# cs301_template.net
KiCad netlist of a schematic drawn in Altium Designer
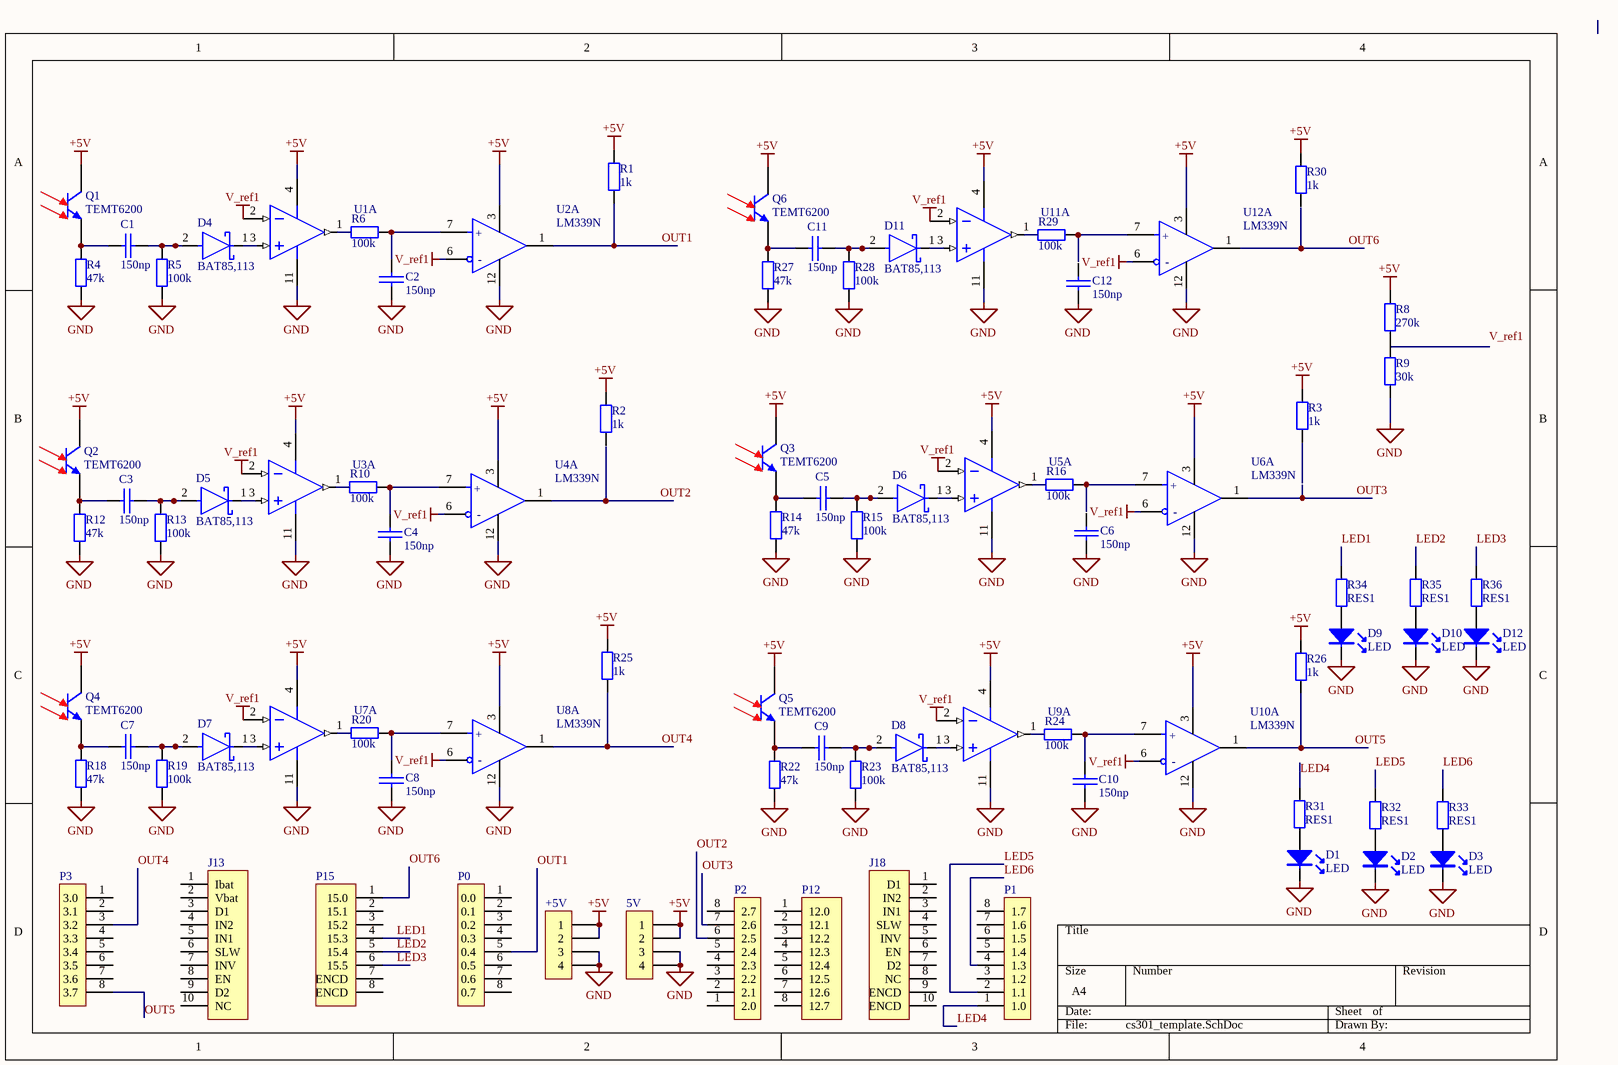
[diagram p0: cs301_template.SchDoc]

(export (version "E")
  (design (tool "Eeschema 10.0.6"))
  (components
    (comp (ref "+5V")
      (value "5V")
      (footprint "IDC4")
      (description "Connector")
      (libsource (lib "Miscellaneous Devices") (part "CON4"))
    )
    (comp (ref "5V")
      (value "5V")
      (footprint "IDC4")
      (description "Connector")
      (libsource (lib "Miscellaneous Devices") (part "CON4"))
    )
    (comp (ref "C1")
      (value "150np")
      (footprint "CCAP-5P0")
      (description "TH ceramic capacitor with 5mm pitch")
      (libsource (lib "COMSYS301_2025") (part "CerCap_TH_5P0"))
    )
    (comp (ref "C2")
      (value "150np")
      (footprint "CCAP-5P0")
      (description "TH ceramic capacitor with 5mm pitch")
      (libsource (lib "COMSYS301_2025") (part "CerCap_TH_5P0"))
    )
    (comp (ref "C3")
      (value "150np")
      (footprint "CCAP-5P0")
      (description "TH ceramic capacitor with 5mm pitch")
      (libsource (lib "COMSYS301_2025") (part "CerCap_TH_5P0"))
    )
    (comp (ref "C4")
      (value "150np")
      (footprint "CCAP-5P0")
      (description "TH ceramic capacitor with 5mm pitch")
      (libsource (lib "COMSYS301_2025") (part "CerCap_TH_5P0"))
    )
    (comp (ref "C5")
      (value "150np")
      (footprint "CCAP-5P0")
      (description "TH ceramic capacitor with 5mm pitch")
      (libsource (lib "COMSYS301_2025") (part "CerCap_TH_5P0"))
    )
    (comp (ref "C6")
      (value "150np")
      (footprint "CCAP-5P0")
      (description "TH ceramic capacitor with 5mm pitch")
      (libsource (lib "COMSYS301_2025") (part "CerCap_TH_5P0"))
    )
    (comp (ref "C7")
      (value "150np")
      (footprint "CCAP-5P0")
      (description "TH ceramic capacitor with 5mm pitch")
      (libsource (lib "COMSYS301_2025") (part "CerCap_TH_5P0"))
    )
    (comp (ref "C8")
      (value "150np")
      (footprint "CCAP-5P0")
      (description "TH ceramic capacitor with 5mm pitch")
      (libsource (lib "COMSYS301_2025") (part "CerCap_TH_5P0"))
    )
    (comp (ref "C9")
      (value "150np")
      (footprint "CCAP-5P0")
      (description "TH ceramic capacitor with 5mm pitch")
      (libsource (lib "COMSYS301_2025") (part "CerCap_TH_5P0"))
    )
    (comp (ref "C10")
      (value "150np")
      (footprint "CCAP-5P0")
      (description "TH ceramic capacitor with 5mm pitch")
      (libsource (lib "COMSYS301_2025") (part "CerCap_TH_5P0"))
    )
    (comp (ref "C11")
      (value "150np")
      (footprint "CCAP-5P0")
      (description "TH ceramic capacitor with 5mm pitch")
      (libsource (lib "COMSYS301_2025") (part "CerCap_TH_5P0"))
    )
    (comp (ref "C12")
      (value "150np")
      (footprint "CCAP-5P0")
      (description "TH ceramic capacitor with 5mm pitch")
      (libsource (lib "COMSYS301_2025") (part "CerCap_TH_5P0"))
    )
    (comp (ref "D1") (value "LED") (footprint "LED0.1/5MM") (libsource (lib "COMSYS301_2013") (part "LED")))
    (comp (ref "D2") (value "LED") (footprint "LED0.1/5MM") (libsource (lib "COMSYS301_2013") (part "LED")))
    (comp (ref "D3") (value "LED") (footprint "LED0.1/5MM") (libsource (lib "COMSYS301_2013") (part "LED")))
    (comp (ref "D4")
      (value "BAT85,113")
      (footprint "FP-SOD68-MFG")
      (description "DIODE SCHOTTKY 30V 200MA DO34")
      (libsource (lib "Components - 18.08.25 - 15.16") (part "CMP-14398-000042-1"))
    )
    (comp (ref "D5")
      (value "BAT85,113")
      (footprint "FP-SOD68-MFG")
      (description "DIODE SCHOTTKY 30V 200MA DO34")
      (libsource (lib "Components - 18.08.25 - 15.16") (part "CMP-14398-000042-1"))
    )
    (comp (ref "D6")
      (value "BAT85,113")
      (footprint "FP-SOD68-MFG")
      (description "DIODE SCHOTTKY 30V 200MA DO34")
      (libsource (lib "Components - 18.08.25 - 15.16") (part "CMP-14398-000042-1"))
    )
    (comp (ref "D7")
      (value "BAT85,113")
      (footprint "FP-SOD68-MFG")
      (description "DIODE SCHOTTKY 30V 200MA DO34")
      (libsource (lib "Components - 18.08.25 - 15.16") (part "CMP-14398-000042-1"))
    )
    (comp (ref "D8")
      (value "BAT85,113")
      (footprint "FP-SOD68-MFG")
      (description "DIODE SCHOTTKY 30V 200MA DO34")
      (libsource (lib "Components - 18.08.25 - 15.16") (part "CMP-14398-000042-1"))
    )
    (comp (ref "D9") (value "LED") (footprint "LED0.1/5MM") (libsource (lib "COMSYS301_2013") (part "LED")))
    (comp (ref "D10") (value "LED") (footprint "LED0.1/5MM") (libsource (lib "COMSYS301_2013") (part "LED")))
    (comp (ref "D11")
      (value "BAT85,113")
      (footprint "FP-SOD68-MFG")
      (description "DIODE SCHOTTKY 30V 200MA DO34")
      (libsource (lib "Components - 18.08.25 - 15.16") (part "CMP-14398-000042-1"))
    )
    (comp (ref "D12") (value "LED") (footprint "LED0.1/5MM") (libsource (lib "COMSYS301_2013") (part "LED")))
    (comp (ref "J13")
      (value "CON10")
      (footprint "idc10")
      (description "Connector")
      (libsource (lib "") (part "CON10_1"))
    )
    (comp (ref "J18")
      (value "CON10")
      (footprint "IDC10")
      (description "Connector")
      (libsource (lib "Miscellaneous Devices") (part "CON10"))
    )
    (comp (ref "P0")
      (value "P0")
      (footprint "idc8")
      (description "Connector")
      (libsource (lib "") (part "CON8_1"))
    )
    (comp (ref "P1")
      (value "P1")
      (footprint "idc8")
      (description "Connector")
      (libsource (lib "") (part "CON8_2"))
    )
    (comp (ref "P2")
      (value "P2")
      (footprint "idc8")
      (description "Connector")
      (libsource (lib "Miscellaneous Devices") (part "CON8"))
    )
    (comp (ref "P3")
      (value "P3")
      (footprint "idc8")
      (description "Connector")
      (libsource (lib "") (part "CON8_1"))
    )
    (comp (ref "P12")
      (value "P12")
      (footprint "idc8")
      (description "Connector")
      (libsource (lib "Miscellaneous Devices") (part "CON8_1"))
    )
    (comp (ref "P15")
      (value "P15")
      (footprint "idc8")
      (description "Connector")
      (libsource (lib "") (part "CON8_1_1"))
    )
    (comp (ref "Q1")
      (value "TEMT6200")
      (footprint "VEMT3700")
      (description "Silicon NPN Phototransistor")
      (libsource (lib "COMSYS301_2025") (part "VEMT3700"))
    )
    (comp (ref "Q2")
      (value "TEMT6200")
      (footprint "VEMT3700")
      (description "Silicon NPN Phototransistor")
      (libsource (lib "COMSYS301_2025") (part "VEMT3700"))
    )
    (comp (ref "Q3")
      (value "TEMT6200")
      (footprint "VEMT3700")
      (description "Silicon NPN Phototransistor")
      (libsource (lib "COMSYS301_2025") (part "VEMT3700"))
    )
    (comp (ref "Q4")
      (value "TEMT6200")
      (footprint "VEMT3700")
      (description "Silicon NPN Phototransistor")
      (libsource (lib "COMSYS301_2025") (part "VEMT3700"))
    )
    (comp (ref "Q5")
      (value "TEMT6200")
      (footprint "VEMT3700")
      (description "Silicon NPN Phototransistor")
      (libsource (lib "COMSYS301_2025") (part "VEMT3700"))
    )
    (comp (ref "Q6")
      (value "TEMT6200")
      (footprint "VEMT3700")
      (description "Silicon NPN Phototransistor")
      (libsource (lib "COMSYS301_2025") (part "VEMT3700"))
    )
    (comp (ref "R1")
      (value "1k")
      (footprint "AXIAL-0.4")
      (description "Through hole resistor")
      (fields (field (name "PUBLISHER") "Altium Limited"))
      (libsource (lib "CS301_Library") (part "Res_TH_0AX4"))
    )
    (comp (ref "R2")
      (value "1k")
      (footprint "AXIAL-0.4")
      (description "Through hole resistor")
      (fields (field (name "PUBLISHER") "Altium Limited"))
      (libsource (lib "CS301_Library") (part "Res_TH_0AX4"))
    )
    (comp (ref "R3")
      (value "1k")
      (footprint "AXIAL-0.4")
      (description "Through hole resistor")
      (fields (field (name "PUBLISHER") "Altium Limited"))
      (libsource (lib "CS301_Library") (part "Res_TH_0AX4"))
    )
    (comp (ref "R4")
      (value "47k")
      (footprint "AXIAL-0.4")
      (description "Through hole resistor")
      (fields (field (name "PUBLISHER") "Altium Limited"))
      (libsource (lib "COMSYS301_2025") (part "Res_TH_0AX4"))
    )
    (comp (ref "R5")
      (value "100k")
      (footprint "AXIAL-0.4")
      (description "Through hole resistor")
      (fields (field (name "PUBLISHER") "Altium Limited"))
      (libsource (lib "COMSYS301_2025") (part "Res_TH_0AX4"))
    )
    (comp (ref "R6")
      (value "100k")
      (footprint "AXIAL-0.4")
      (description "Through hole resistor")
      (fields (field (name "PUBLISHER") "Altium Limited"))
      (libsource (lib "") (part "Res_TH_0AX4_1"))
    )
    (comp (ref "R8")
      (value "270k")
      (footprint "AXIAL-0.4")
      (description "Through hole resistor")
      (fields (field (name "PUBLISHER") "Altium Limited"))
      (libsource (lib "") (part "Res_TH_0AX4_2"))
    )
    (comp (ref "R9")
      (value "30k")
      (footprint "AXIAL-0.4")
      (description "Through hole resistor")
      (fields (field (name "PUBLISHER") "Altium Limited"))
      (libsource (lib "") (part "Res_TH_0AX4_2"))
    )
    (comp (ref "R10")
      (value "100k")
      (footprint "AXIAL-0.4")
      (description "Through hole resistor")
      (fields (field (name "PUBLISHER") "Altium Limited"))
      (libsource (lib "") (part "Res_TH_0AX4_1"))
    )
    (comp (ref "R12")
      (value "47k")
      (footprint "AXIAL-0.4")
      (description "Through hole resistor")
      (fields (field (name "PUBLISHER") "Altium Limited"))
      (libsource (lib "COMSYS301_2025") (part "Res_TH_0AX4"))
    )
    (comp (ref "R13")
      (value "100k")
      (footprint "AXIAL-0.4")
      (description "Through hole resistor")
      (fields (field (name "PUBLISHER") "Altium Limited"))
      (libsource (lib "COMSYS301_2025") (part "Res_TH_0AX4"))
    )
    (comp (ref "R14")
      (value "47k")
      (footprint "AXIAL-0.4")
      (description "Through hole resistor")
      (fields (field (name "PUBLISHER") "Altium Limited"))
      (libsource (lib "COMSYS301_2025") (part "Res_TH_0AX4"))
    )
    (comp (ref "R15")
      (value "100k")
      (footprint "AXIAL-0.4")
      (description "Through hole resistor")
      (fields (field (name "PUBLISHER") "Altium Limited"))
      (libsource (lib "COMSYS301_2025") (part "Res_TH_0AX4"))
    )
    (comp (ref "R16")
      (value "100k")
      (footprint "AXIAL-0.4")
      (description "Through hole resistor")
      (fields (field (name "PUBLISHER") "Altium Limited"))
      (libsource (lib "") (part "Res_TH_0AX4_1"))
    )
    (comp (ref "R18")
      (value "47k")
      (footprint "AXIAL-0.4")
      (description "Through hole resistor")
      (fields (field (name "PUBLISHER") "Altium Limited"))
      (libsource (lib "COMSYS301_2025") (part "Res_TH_0AX4"))
    )
    (comp (ref "R19")
      (value "100k")
      (footprint "AXIAL-0.4")
      (description "Through hole resistor")
      (fields (field (name "PUBLISHER") "Altium Limited"))
      (libsource (lib "COMSYS301_2025") (part "Res_TH_0AX4"))
    )
    (comp (ref "R20")
      (value "100k")
      (footprint "AXIAL-0.4")
      (description "Through hole resistor")
      (fields (field (name "PUBLISHER") "Altium Limited"))
      (libsource (lib "") (part "Res_TH_0AX4_1"))
    )
    (comp (ref "R22")
      (value "47k")
      (footprint "AXIAL-0.4")
      (description "Through hole resistor")
      (fields (field (name "PUBLISHER") "Altium Limited"))
      (libsource (lib "COMSYS301_2025") (part "Res_TH_0AX4"))
    )
    (comp (ref "R23")
      (value "100k")
      (footprint "AXIAL-0.4")
      (description "Through hole resistor")
      (fields (field (name "PUBLISHER") "Altium Limited"))
      (libsource (lib "COMSYS301_2025") (part "Res_TH_0AX4"))
    )
    (comp (ref "R24")
      (value "100k")
      (footprint "AXIAL-0.4")
      (description "Through hole resistor")
      (fields (field (name "PUBLISHER") "Altium Limited"))
      (libsource (lib "") (part "Res_TH_0AX4_1"))
    )
    (comp (ref "R25")
      (value "1k")
      (footprint "AXIAL-0.4")
      (description "Through hole resistor")
      (fields (field (name "PUBLISHER") "Altium Limited"))
      (libsource (lib "CS301_Library") (part "Res_TH_0AX4"))
    )
    (comp (ref "R26")
      (value "1k")
      (footprint "AXIAL-0.4")
      (description "Through hole resistor")
      (fields (field (name "PUBLISHER") "Altium Limited"))
      (libsource (lib "CS301_Library") (part "Res_TH_0AX4"))
    )
    (comp (ref "R27")
      (value "47k")
      (footprint "AXIAL-0.4")
      (description "Through hole resistor")
      (fields (field (name "PUBLISHER") "Altium Limited"))
      (libsource (lib "COMSYS301_2025") (part "Res_TH_0AX4"))
    )
    (comp (ref "R28")
      (value "100k")
      (footprint "AXIAL-0.4")
      (description "Through hole resistor")
      (fields (field (name "PUBLISHER") "Altium Limited"))
      (libsource (lib "COMSYS301_2025") (part "Res_TH_0AX4"))
    )
    (comp (ref "R29")
      (value "100k")
      (footprint "AXIAL-0.4")
      (description "Through hole resistor")
      (fields (field (name "PUBLISHER") "Altium Limited"))
      (libsource (lib "") (part "Res_TH_0AX4_1"))
    )
    (comp (ref "R30")
      (value "1k")
      (footprint "AXIAL-0.4")
      (description "Through hole resistor")
      (fields (field (name "PUBLISHER") "Altium Limited"))
      (libsource (lib "CS301_Library") (part "Res_TH_0AX4"))
    )
    (comp (ref "R31")
      (value "RES1")
      (footprint "AXIAL-0.4")
      (description "Through hole resistor")
      (fields (field (name "PUBLISHER") "Altium Limited"))
      (libsource (lib "CS301_Library") (part "Res_TH_0AX4"))
    )
    (comp (ref "R32")
      (value "RES1")
      (footprint "AXIAL-0.4")
      (description "Through hole resistor")
      (fields (field (name "PUBLISHER") "Altium Limited"))
      (libsource (lib "CS301_Library") (part "Res_TH_0AX4"))
    )
    (comp (ref "R33")
      (value "RES1")
      (footprint "AXIAL-0.4")
      (description "Through hole resistor")
      (fields (field (name "PUBLISHER") "Altium Limited"))
      (libsource (lib "CS301_Library") (part "Res_TH_0AX4"))
    )
    (comp (ref "R34")
      (value "RES1")
      (footprint "AXIAL-0.4")
      (description "Through hole resistor")
      (fields (field (name "PUBLISHER") "Altium Limited"))
      (libsource (lib "CS301_Library") (part "Res_TH_0AX4"))
    )
    (comp (ref "R35")
      (value "RES1")
      (footprint "AXIAL-0.4")
      (description "Through hole resistor")
      (fields (field (name "PUBLISHER") "Altium Limited"))
      (libsource (lib "CS301_Library") (part "Res_TH_0AX4"))
    )
    (comp (ref "R36")
      (value "RES1")
      (footprint "AXIAL-0.4")
      (description "Through hole resistor")
      (fields (field (name "PUBLISHER") "Altium Limited"))
      (libsource (lib "CS301_Library") (part "Res_TH_0AX4"))
    )
    (comp (ref "U1")
      (value "LM324")
      (footprint "DIP-14")
      (description "IC OPAMP GP 14DIP")
      (fields
        (field (name "MANUFACTURER") "ON Semiconductor")
        (field (name "MANUFACTURER PART NUMBER") "LM324N")
      )
      (libsource (lib "COMSYS301_2025") (part "LM324N_TH_DIP16"))
    )
    (comp (ref "U2")
      (value "LM339N")
      (footprint "FP-N0014A-MFG")
      (description "IC QUAD DIFF COMPARATOR 14-DIP")
      (libsource (lib "Components - 18.08.25 - 15.06") (part "CMP-0055-00143-4"))
    )
    (comp (ref "U3")
      (value "LM324")
      (footprint "DIP-14")
      (description "IC OPAMP GP 14DIP")
      (fields
        (field (name "MANUFACTURER") "ON Semiconductor")
        (field (name "MANUFACTURER PART NUMBER") "LM324N")
      )
      (libsource (lib "COMSYS301_2025") (part "LM324N_TH_DIP16"))
    )
    (comp (ref "U4")
      (value "LM339N")
      (footprint "FP-N0014A-MFG")
      (description "IC QUAD DIFF COMPARATOR 14-DIP")
      (libsource (lib "Components - 18.08.25 - 15.06") (part "CMP-0055-00143-4"))
    )
    (comp (ref "U5")
      (value "LM324")
      (footprint "DIP-14")
      (description "IC OPAMP GP 14DIP")
      (fields
        (field (name "MANUFACTURER") "ON Semiconductor")
        (field (name "MANUFACTURER PART NUMBER") "LM324N")
      )
      (libsource (lib "COMSYS301_2025") (part "LM324N_TH_DIP16"))
    )
    (comp (ref "U6")
      (value "LM339N")
      (footprint "FP-N0014A-MFG")
      (description "IC QUAD DIFF COMPARATOR 14-DIP")
      (libsource (lib "Components - 18.08.25 - 15.06") (part "CMP-0055-00143-4"))
    )
    (comp (ref "U7")
      (value "LM324")
      (footprint "DIP-14")
      (description "IC OPAMP GP 14DIP")
      (fields
        (field (name "MANUFACTURER") "ON Semiconductor")
        (field (name "MANUFACTURER PART NUMBER") "LM324N")
      )
      (libsource (lib "COMSYS301_2025") (part "LM324N_TH_DIP16"))
    )
    (comp (ref "U8")
      (value "LM339N")
      (footprint "FP-N0014A-MFG")
      (description "IC QUAD DIFF COMPARATOR 14-DIP")
      (libsource (lib "Components - 18.08.25 - 15.06") (part "CMP-0055-00143-4"))
    )
    (comp (ref "U9")
      (value "LM324")
      (footprint "DIP-14")
      (description "IC OPAMP GP 14DIP")
      (fields
        (field (name "MANUFACTURER") "ON Semiconductor")
        (field (name "MANUFACTURER PART NUMBER") "LM324N")
      )
      (libsource (lib "COMSYS301_2025") (part "LM324N_TH_DIP16"))
    )
    (comp (ref "U10")
      (value "LM339N")
      (footprint "FP-N0014A-MFG")
      (description "IC QUAD DIFF COMPARATOR 14-DIP")
      (libsource (lib "Components - 18.08.25 - 15.06") (part "CMP-0055-00143-4"))
    )
    (comp (ref "U11")
      (value "LM324")
      (footprint "DIP-14")
      (description "IC OPAMP GP 14DIP")
      (fields
        (field (name "MANUFACTURER") "ON Semiconductor")
        (field (name "MANUFACTURER PART NUMBER") "LM324N")
      )
      (libsource (lib "COMSYS301_2025") (part "LM324N_TH_DIP16"))
    )
    (comp (ref "U12")
      (value "LM339N")
      (footprint "FP-N0014A-MFG")
      (description "IC QUAD DIFF COMPARATOR 14-DIP")
      (libsource (lib "Components - 18.08.25 - 15.06") (part "CMP-0055-00143-4"))
    )
  )
  (nets
    (net (code "1") (name "+5V") (class "Default")
      (node (ref "+5V") (pin "1") (pinfunction "1_1") (pintype "passive"))
      (node (ref "+5V") (pin "2") (pinfunction "2_2") (pintype "passive"))
      (node (ref "5V") (pin "1") (pinfunction "1_1") (pintype "passive"))
      (node (ref "5V") (pin "2") (pinfunction "2_2") (pintype "passive"))
      (node (ref "Q1") (pin "1") (pinfunction "C_1") (pintype "passive"))
      (node (ref "Q2") (pin "1") (pinfunction "C_1") (pintype "passive"))
      (node (ref "Q3") (pin "1") (pinfunction "C_1") (pintype "passive"))
      (node (ref "Q4") (pin "1") (pinfunction "C_1") (pintype "passive"))
      (node (ref "Q5") (pin "1") (pinfunction "C_1") (pintype "passive"))
      (node (ref "Q6") (pin "1") (pinfunction "C_1") (pintype "passive"))
      (node (ref "R1") (pin "2") (pinfunction "2_2") (pintype "passive"))
      (node (ref "R2") (pin "2") (pinfunction "2_2") (pintype "passive"))
      (node (ref "R25") (pin "2") (pinfunction "2_2") (pintype "passive"))
      (node (ref "R26") (pin "2") (pinfunction "2_2") (pintype "passive"))
      (node (ref "R3") (pin "2") (pinfunction "2_2") (pintype "passive"))
      (node (ref "R30") (pin "2") (pinfunction "2_2") (pintype "passive"))
      (node (ref "R8") (pin "1") (pinfunction "1_1") (pintype "passive"))
      (node (ref "U1") (pin "4") (pinfunction "VDD_4") (pintype "power_in"))
      (node (ref "U10") (pin "3") (pinfunction "VCC_3") (pintype "power_in"))
      (node (ref "U11") (pin "4") (pinfunction "VDD_4") (pintype "power_in"))
      (node (ref "U12") (pin "3") (pinfunction "VCC_3") (pintype "power_in"))
      (node (ref "U2") (pin "3") (pinfunction "VCC_3") (pintype "power_in"))
      (node (ref "U3") (pin "4") (pinfunction "VDD_4") (pintype "power_in"))
      (node (ref "U4") (pin "3") (pinfunction "VCC_3") (pintype "power_in"))
      (node (ref "U5") (pin "4") (pinfunction "VDD_4") (pintype "power_in"))
      (node (ref "U6") (pin "3") (pinfunction "VCC_3") (pintype "power_in"))
      (node (ref "U7") (pin "4") (pinfunction "VDD_4") (pintype "power_in"))
      (node (ref "U8") (pin "3") (pinfunction "VCC_3") (pintype "power_in"))
      (node (ref "U9") (pin "4") (pinfunction "VDD_4") (pintype "power_in"))
    )
    (net (code "2") (name "/LED1") (class "Default")
      (node (ref "P15") (pin "4") (pinfunction "15.3_4") (pintype "passive"))
      (node (ref "R34") (pin "2") (pinfunction "2_2") (pintype "passive"))
    )
    (net (code "3") (name "/LED2") (class "Default")
      (node (ref "P15") (pin "5") (pinfunction "15.4_5") (pintype "passive"))
      (node (ref "R35") (pin "2") (pinfunction "2_2") (pintype "passive"))
    )
    (net (code "4") (name "/LED3") (class "Default")
      (node (ref "P15") (pin "6") (pinfunction "15.5_6") (pintype "passive"))
      (node (ref "R36") (pin "2") (pinfunction "2_2") (pintype "passive"))
    )
    (net (code "5") (name "/LED4") (class "Default")
      (node (ref "P1") (pin "1") (pinfunction "1.0_1") (pintype "passive"))
      (node (ref "R31") (pin "2") (pinfunction "2_2") (pintype "passive"))
    )
    (net (code "6") (name "/LED5") (class "Default")
      (node (ref "P1") (pin "2") (pinfunction "1.1_2") (pintype "passive"))
      (node (ref "R32") (pin "2") (pinfunction "2_2") (pintype "passive"))
    )
    (net (code "7") (name "/LED6") (class "Default")
      (node (ref "P1") (pin "4") (pinfunction "1.3_4") (pintype "passive"))
      (node (ref "R33") (pin "2") (pinfunction "2_2") (pintype "passive"))
    )
    (net (code "8") (name "/OUT1") (class "Default")
      (node (ref "P0") (pin "5") (pinfunction "3.4_5") (pintype "passive"))
      (node (ref "R1") (pin "1") (pinfunction "1_1") (pintype "passive"))
      (node (ref "U2") (pin "1") (pinfunction "1OUT_1") (pintype "passive"))
    )
    (net (code "9") (name "/OUT2") (class "Default")
      (node (ref "P2") (pin "6") (pinfunction "2.5_6") (pintype "passive"))
      (node (ref "U4") (pin "1") (pinfunction "1OUT_1") (pintype "passive"))
    )
    (net (code "10") (name "/OUT3") (class "Default")
      (node (ref "P2") (pin "7") (pinfunction "2.6_7") (pintype "passive"))
      (node (ref "U6") (pin "1") (pinfunction "1OUT_1") (pintype "passive"))
    )
    (net (code "11") (name "/OUT4") (class "Default")
      (node (ref "P3") (pin "3") (pinfunction "3.2_3") (pintype "passive"))
      (node (ref "R25") (pin "1") (pinfunction "1_1") (pintype "passive"))
      (node (ref "U8") (pin "1") (pinfunction "1OUT_1") (pintype "passive"))
    )
    (net (code "12") (name "/OUT5") (class "Default")
      (node (ref "P3") (pin "8") (pinfunction "3.7_8") (pintype "passive"))
      (node (ref "R26") (pin "1") (pinfunction "1_1") (pintype "passive"))
      (node (ref "U10") (pin "1") (pinfunction "1OUT_1") (pintype "passive"))
    )
    (net (code "13") (name "/OUT6") (class "Default")
      (node (ref "P15") (pin "1") (pinfunction "15.0_1") (pintype "passive"))
      (node (ref "U12") (pin "1") (pinfunction "1OUT_1") (pintype "passive"))
    )
    (net (code "14") (name "GND") (class "Default")
      (node (ref "+5V") (pin "3") (pinfunction "3_3") (pintype "passive"))
      (node (ref "+5V") (pin "4") (pinfunction "4_4") (pintype "passive"))
      (node (ref "5V") (pin "3") (pinfunction "3_3") (pintype "passive"))
      (node (ref "5V") (pin "4") (pinfunction "4_4") (pintype "passive"))
      (node (ref "C10") (pin "2") (pinfunction "2_2") (pintype "passive"))
      (node (ref "C2") (pin "2") (pinfunction "2_2") (pintype "passive"))
      (node (ref "C4") (pin "2") (pinfunction "2_2") (pintype "passive"))
      (node (ref "C8") (pin "2") (pinfunction "2_2") (pintype "passive"))
      (node (ref "D1") (pin "K") (pinfunction "2_K") (pintype "passive"))
      (node (ref "D10") (pin "K") (pinfunction "2_K") (pintype "passive"))
      (node (ref "D12") (pin "K") (pinfunction "2_K") (pintype "passive"))
      (node (ref "D2") (pin "K") (pinfunction "2_K") (pintype "passive"))
      (node (ref "D3") (pin "K") (pinfunction "2_K") (pintype "passive"))
      (node (ref "D9") (pin "K") (pinfunction "2_K") (pintype "passive"))
      (node (ref "R12") (pin "1") (pinfunction "1_1") (pintype "passive"))
      (node (ref "R13") (pin "1") (pinfunction "1_1") (pintype "passive"))
      (node (ref "R14") (pin "1") (pinfunction "1_1") (pintype "passive"))
      (node (ref "R15") (pin "1") (pinfunction "1_1") (pintype "passive"))
      (node (ref "R18") (pin "1") (pinfunction "1_1") (pintype "passive"))
      (node (ref "R19") (pin "1") (pinfunction "1_1") (pintype "passive"))
      (node (ref "R22") (pin "1") (pinfunction "1_1") (pintype "passive"))
      (node (ref "R23") (pin "1") (pinfunction "1_1") (pintype "passive"))
      (node (ref "R27") (pin "1") (pinfunction "1_1") (pintype "passive"))
      (node (ref "R28") (pin "1") (pinfunction "1_1") (pintype "passive"))
      (node (ref "R4") (pin "1") (pinfunction "1_1") (pintype "passive"))
      (node (ref "R5") (pin "1") (pinfunction "1_1") (pintype "passive"))
      (node (ref "R9") (pin "2") (pinfunction "2_2") (pintype "passive"))
      (node (ref "U1") (pin "11") (pinfunction "VSS_11") (pintype "power_in"))
      (node (ref "U10") (pin "12") (pinfunction "GND_12") (pintype "power_in"))
      (node (ref "U11") (pin "11") (pinfunction "VSS_11") (pintype "power_in"))
      (node (ref "U12") (pin "12") (pinfunction "GND_12") (pintype "power_in"))
      (node (ref "U2") (pin "12") (pinfunction "GND_12") (pintype "power_in"))
      (node (ref "U3") (pin "11") (pinfunction "VSS_11") (pintype "power_in"))
      (node (ref "U4") (pin "12") (pinfunction "GND_12") (pintype "power_in"))
      (node (ref "U5") (pin "11") (pinfunction "VSS_11") (pintype "power_in"))
      (node (ref "U6") (pin "12") (pinfunction "GND_12") (pintype "power_in"))
      (node (ref "U7") (pin "11") (pinfunction "VSS_11") (pintype "power_in"))
      (node (ref "U8") (pin "12") (pinfunction "GND_12") (pintype "power_in"))
      (node (ref "U9") (pin "11") (pinfunction "VSS_11") (pintype "power_in"))
    )
    (net (code "15") (name "Net-(D1-1)") (class "Default")
      (node (ref "D1") (pin "A") (pinfunction "1_A") (pintype "passive"))
      (node (ref "R31") (pin "1") (pinfunction "1_1") (pintype "passive"))
    )
    (net (code "16") (name "Net-(D2-1)") (class "Default")
      (node (ref "D2") (pin "A") (pinfunction "1_A") (pintype "passive"))
      (node (ref "R32") (pin "1") (pinfunction "1_1") (pintype "passive"))
    )
    (net (code "17") (name "Net-(D3-1)") (class "Default")
      (node (ref "D3") (pin "A") (pinfunction "1_A") (pintype "passive"))
      (node (ref "R33") (pin "1") (pinfunction "1_1") (pintype "passive"))
    )
    (net (code "18") (name "Net-(D4-A)") (class "Default")
      (node (ref "C1") (pin "2") (pinfunction "2_2") (pintype "passive"))
      (node (ref "D4") (pin "2") (pinfunction "A_2") (pintype "passive"))
      (node (ref "R5") (pin "2") (pinfunction "2_2") (pintype "passive"))
    )
    (net (code "19") (name "Net-(D4-C)") (class "Default")
      (node (ref "D4") (pin "1") (pinfunction "C_1") (pintype "passive"))
      (node (ref "U1") (pin "3") (pinfunction "VINA+_3") (pintype "input"))
    )
    (net (code "20") (name "Net-(D5-A)") (class "Default")
      (node (ref "C3") (pin "2") (pinfunction "2_2") (pintype "passive"))
      (node (ref "D5") (pin "2") (pinfunction "A_2") (pintype "passive"))
      (node (ref "R13") (pin "2") (pinfunction "2_2") (pintype "passive"))
    )
    (net (code "21") (name "Net-(D5-C)") (class "Default")
      (node (ref "D5") (pin "1") (pinfunction "C_1") (pintype "passive"))
      (node (ref "U3") (pin "3") (pinfunction "VINA+_3") (pintype "input"))
    )
    (net (code "22") (name "Net-(D6-A)") (class "Default")
      (node (ref "C5") (pin "2") (pinfunction "2_2") (pintype "passive"))
      (node (ref "D6") (pin "2") (pinfunction "A_2") (pintype "passive"))
      (node (ref "R15") (pin "2") (pinfunction "2_2") (pintype "passive"))
    )
    (net (code "23") (name "Net-(D6-C)") (class "Default")
      (node (ref "D6") (pin "1") (pinfunction "C_1") (pintype "passive"))
      (node (ref "U5") (pin "3") (pinfunction "VINA+_3") (pintype "input"))
    )
    (net (code "24") (name "Net-(D7-A)") (class "Default")
      (node (ref "C7") (pin "2") (pinfunction "2_2") (pintype "passive"))
      (node (ref "D7") (pin "2") (pinfunction "A_2") (pintype "passive"))
      (node (ref "R19") (pin "2") (pinfunction "2_2") (pintype "passive"))
    )
    (net (code "25") (name "Net-(D7-C)") (class "Default")
      (node (ref "D7") (pin "1") (pinfunction "C_1") (pintype "passive"))
      (node (ref "U7") (pin "3") (pinfunction "VINA+_3") (pintype "input"))
    )
    (net (code "26") (name "Net-(D8-A)") (class "Default")
      (node (ref "C9") (pin "2") (pinfunction "2_2") (pintype "passive"))
      (node (ref "D8") (pin "2") (pinfunction "A_2") (pintype "passive"))
      (node (ref "R23") (pin "2") (pinfunction "2_2") (pintype "passive"))
    )
    (net (code "27") (name "Net-(D8-C)") (class "Default")
      (node (ref "D8") (pin "1") (pinfunction "C_1") (pintype "passive"))
      (node (ref "U9") (pin "3") (pinfunction "VINA+_3") (pintype "input"))
    )
    (net (code "28") (name "Net-(D9-1)") (class "Default")
      (node (ref "D9") (pin "A") (pinfunction "1_A") (pintype "passive"))
      (node (ref "R34") (pin "1") (pinfunction "1_1") (pintype "passive"))
    )
    (net (code "29") (name "Net-(D10-1)") (class "Default")
      (node (ref "D10") (pin "A") (pinfunction "1_A") (pintype "passive"))
      (node (ref "R35") (pin "1") (pinfunction "1_1") (pintype "passive"))
    )
    (net (code "30") (name "Net-(D11-A)") (class "Default")
      (node (ref "C11") (pin "2") (pinfunction "2_2") (pintype "passive"))
      (node (ref "D11") (pin "2") (pinfunction "A_2") (pintype "passive"))
      (node (ref "R28") (pin "2") (pinfunction "2_2") (pintype "passive"))
    )
    (net (code "31") (name "Net-(D11-C)") (class "Default")
      (node (ref "D11") (pin "1") (pinfunction "C_1") (pintype "passive"))
      (node (ref "U11") (pin "3") (pinfunction "VINA+_3") (pintype "input"))
    )
    (net (code "32") (name "Net-(D12-1)") (class "Default")
      (node (ref "D12") (pin "A") (pinfunction "1_A") (pintype "passive"))
      (node (ref "R36") (pin "1") (pinfunction "1_1") (pintype "passive"))
    )
    (net (code "33") (name "Net-(Q1-E)") (class "Default")
      (node (ref "C1") (pin "1") (pinfunction "1_1") (pintype "passive"))
      (node (ref "Q1") (pin "2") (pinfunction "E_2") (pintype "passive"))
      (node (ref "R4") (pin "2") (pinfunction "2_2") (pintype "passive"))
    )
    (net (code "34") (name "Net-(Q2-E)") (class "Default")
      (node (ref "C3") (pin "1") (pinfunction "1_1") (pintype "passive"))
      (node (ref "Q2") (pin "2") (pinfunction "E_2") (pintype "passive"))
      (node (ref "R12") (pin "2") (pinfunction "2_2") (pintype "passive"))
    )
    (net (code "35") (name "Net-(Q3-E)") (class "Default")
      (node (ref "C5") (pin "1") (pinfunction "1_1") (pintype "passive"))
      (node (ref "Q3") (pin "2") (pinfunction "E_2") (pintype "passive"))
      (node (ref "R14") (pin "2") (pinfunction "2_2") (pintype "passive"))
    )
    (net (code "36") (name "Net-(Q4-E)") (class "Default")
      (node (ref "C7") (pin "1") (pinfunction "1_1") (pintype "passive"))
      (node (ref "Q4") (pin "2") (pinfunction "E_2") (pintype "passive"))
      (node (ref "R18") (pin "2") (pinfunction "2_2") (pintype "passive"))
    )
    (net (code "37") (name "Net-(Q5-E)") (class "Default")
      (node (ref "C9") (pin "1") (pinfunction "1_1") (pintype "passive"))
      (node (ref "Q5") (pin "2") (pinfunction "E_2") (pintype "passive"))
      (node (ref "R22") (pin "2") (pinfunction "2_2") (pintype "passive"))
    )
    (net (code "38") (name "Net-(Q6-E)") (class "Default")
      (node (ref "C11") (pin "1") (pinfunction "1_1") (pintype "passive"))
      (node (ref "Q6") (pin "2") (pinfunction "E_2") (pintype "passive"))
      (node (ref "R27") (pin "2") (pinfunction "2_2") (pintype "passive"))
    )
    (net (code "39") (name "Net-(R8-Pad2)") (class "Default")
      (node (ref "R8") (pin "2") (pinfunction "2_2") (pintype "passive"))
      (node (ref "R9") (pin "1") (pinfunction "1_1") (pintype "passive"))
    )
    (net (code "40") (name "Net-(U1A-VOUTA)") (class "Default")
      (node (ref "R6") (pin "2") (pinfunction "2_2") (pintype "passive"))
      (node (ref "U1") (pin "1") (pinfunction "VOUTA_1") (pintype "output"))
    )
    (net (code "41") (name "Net-(U2A-1IN+)") (class "Default")
      (node (ref "C2") (pin "1") (pinfunction "1_1") (pintype "passive"))
      (node (ref "R6") (pin "1") (pinfunction "1_1") (pintype "passive"))
      (node (ref "U2") (pin "7") (pinfunction "1IN+_7") (pintype "tri_state"))
    )
    (net (code "42") (name "Net-(U3A-VOUTA)") (class "Default")
      (node (ref "R10") (pin "2") (pinfunction "2_2") (pintype "passive"))
      (node (ref "U3") (pin "1") (pinfunction "VOUTA_1") (pintype "output"))
    )
    (net (code "43") (name "Net-(U4A-1IN+)") (class "Default")
      (node (ref "C4") (pin "1") (pinfunction "1_1") (pintype "passive"))
      (node (ref "R10") (pin "1") (pinfunction "1_1") (pintype "passive"))
      (node (ref "U4") (pin "7") (pinfunction "1IN+_7") (pintype "tri_state"))
    )
    (net (code "44") (name "Net-(U5A-VOUTA)") (class "Default")
      (node (ref "R16") (pin "2") (pinfunction "2_2") (pintype "passive"))
      (node (ref "U5") (pin "1") (pinfunction "VOUTA_1") (pintype "output"))
    )
    (net (code "45") (name "Net-(U6A-1IN+)") (class "Default")
      (node (ref "R16") (pin "1") (pinfunction "1_1") (pintype "passive"))
      (node (ref "U6") (pin "7") (pinfunction "1IN+_7") (pintype "tri_state"))
    )
    (net (code "46") (name "Net-(U7A-VOUTA)") (class "Default")
      (node (ref "R20") (pin "2") (pinfunction "2_2") (pintype "passive"))
      (node (ref "U7") (pin "1") (pinfunction "VOUTA_1") (pintype "output"))
    )
    (net (code "47") (name "Net-(U8A-1IN+)") (class "Default")
      (node (ref "C8") (pin "1") (pinfunction "1_1") (pintype "passive"))
      (node (ref "R20") (pin "1") (pinfunction "1_1") (pintype "passive"))
      (node (ref "U8") (pin "7") (pinfunction "1IN+_7") (pintype "tri_state"))
    )
    (net (code "48") (name "Net-(U9A-VOUTA)") (class "Default")
      (node (ref "R24") (pin "2") (pinfunction "2_2") (pintype "passive"))
      (node (ref "U9") (pin "1") (pinfunction "VOUTA_1") (pintype "output"))
    )
    (net (code "49") (name "Net-(U10A-1IN+)") (class "Default")
      (node (ref "C10") (pin "1") (pinfunction "1_1") (pintype "passive"))
      (node (ref "R24") (pin "1") (pinfunction "1_1") (pintype "passive"))
      (node (ref "U10") (pin "7") (pinfunction "1IN+_7") (pintype "tri_state"))
    )
    (net (code "50") (name "Net-(U11A-VOUTA)") (class "Default")
      (node (ref "R29") (pin "2") (pinfunction "2_2") (pintype "passive"))
      (node (ref "U11") (pin "1") (pinfunction "VOUTA_1") (pintype "output"))
    )
    (net (code "51") (name "Net-(U12A-1IN+)") (class "Default")
      (node (ref "R29") (pin "1") (pinfunction "1_1") (pintype "passive"))
      (node (ref "U12") (pin "7") (pinfunction "1IN+_7") (pintype "tri_state"))
    )
    (net (code "52") (name "V_ref1") (class "Default")
      (node (ref "U1") (pin "2") (pinfunction "VINA-_2") (pintype "input"))
      (node (ref "U10") (pin "6") (pinfunction "1IN-_6") (pintype "tri_state"))
      (node (ref "U11") (pin "2") (pinfunction "VINA-_2") (pintype "input"))
      (node (ref "U12") (pin "6") (pinfunction "1IN-_6") (pintype "tri_state"))
      (node (ref "U2") (pin "6") (pinfunction "1IN-_6") (pintype "tri_state"))
      (node (ref "U3") (pin "2") (pinfunction "VINA-_2") (pintype "input"))
      (node (ref "U4") (pin "6") (pinfunction "1IN-_6") (pintype "tri_state"))
      (node (ref "U5") (pin "2") (pinfunction "VINA-_2") (pintype "input"))
      (node (ref "U6") (pin "6") (pinfunction "1IN-_6") (pintype "tri_state"))
      (node (ref "U7") (pin "2") (pinfunction "VINA-_2") (pintype "input"))
      (node (ref "U8") (pin "6") (pinfunction "1IN-_6") (pintype "tri_state"))
      (node (ref "U9") (pin "2") (pinfunction "VINA-_2") (pintype "input"))
    )
    (net (code "53") (name "unconnected-(C6-Pad1)") (class "Default")
      (node (ref "C6") (pin "1") (pinfunction "1_1") (pintype "passive"))
    )
    (net (code "54") (name "unconnected-(C6-Pad2)") (class "Default")
      (node (ref "C6") (pin "2") (pinfunction "2_2") (pintype "passive"))
    )
    (net (code "55") (name "unconnected-(C12-Pad1)") (class "Default")
      (node (ref "C12") (pin "1") (pinfunction "1_1") (pintype "passive"))
    )
    (net (code "56") (name "unconnected-(C12-Pad2)") (class "Default")
      (node (ref "C12") (pin "2") (pinfunction "2_2") (pintype "passive"))
    )
    (net (code "57") (name "unconnected-(J13-D1-Pad3)") (class "Default")
      (node (ref "J13") (pin "3") (pinfunction "D1_3") (pintype "passive"))
    )
    (net (code "58") (name "unconnected-(J13-D2-Pad9)") (class "Default")
      (node (ref "J13") (pin "9") (pinfunction "D2_9") (pintype "passive"))
    )
    (net (code "59") (name "unconnected-(J13-EN-Pad8)") (class "Default")
      (node (ref "J13") (pin "8") (pinfunction "EN_8") (pintype "passive"))
    )
    (net (code "60") (name "unconnected-(J13-IN1-Pad5)") (class "Default")
      (node (ref "J13") (pin "5") (pinfunction "IN1_5") (pintype "passive"))
    )
    (net (code "61") (name "unconnected-(J13-IN2-Pad4)") (class "Default")
      (node (ref "J13") (pin "4") (pinfunction "IN2_4") (pintype "passive"))
    )
    (net (code "62") (name "unconnected-(J13-INV-Pad7)") (class "Default")
      (node (ref "J13") (pin "7") (pinfunction "INV_7") (pintype "passive"))
    )
    (net (code "63") (name "unconnected-(J13-Ibat-Pad1)") (class "Default")
      (node (ref "J13") (pin "1") (pinfunction "Ibat_1") (pintype "passive"))
    )
    (net (code "64") (name "unconnected-(J13-NC-Pad10)") (class "Default")
      (node (ref "J13") (pin "10") (pinfunction "NC_10") (pintype "passive"))
    )
    (net (code "65") (name "unconnected-(J13-SLW-Pad6)") (class "Default")
      (node (ref "J13") (pin "6") (pinfunction "SLW_6") (pintype "passive"))
    )
    (net (code "66") (name "unconnected-(J13-Vbat-Pad2)") (class "Default")
      (node (ref "J13") (pin "2") (pinfunction "Vbat_2") (pintype "passive"))
    )
    (net (code "67") (name "unconnected-(J18-D1-Pad1)") (class "Default")
      (node (ref "J18") (pin "1") (pinfunction "D1_1") (pintype "passive"))
    )
    (net (code "68") (name "unconnected-(J18-D2-Pad7)") (class "Default")
      (node (ref "J18") (pin "7") (pinfunction "D2_7") (pintype "passive"))
    )
    (net (code "69") (name "unconnected-(J18-EN-Pad6)") (class "Default")
      (node (ref "J18") (pin "6") (pinfunction "EN_6") (pintype "passive"))
    )
    (net (code "70") (name "unconnected-(J18-ENCD-Pad9)") (class "Default")
      (node (ref "J18") (pin "9") (pinfunction "ENCD_9") (pintype "passive"))
    )
    (net (code "71") (name "unconnected-(J18-ENCD-Pad10)") (class "Default")
      (node (ref "J18") (pin "10") (pinfunction "ENCD_10") (pintype "passive"))
    )
    (net (code "72") (name "unconnected-(J18-IN1-Pad3)") (class "Default")
      (node (ref "J18") (pin "3") (pinfunction "IN1_3") (pintype "passive"))
    )
    (net (code "73") (name "unconnected-(J18-IN2-Pad2)") (class "Default")
      (node (ref "J18") (pin "2") (pinfunction "IN2_2") (pintype "passive"))
    )
    (net (code "74") (name "unconnected-(J18-INV-Pad5)") (class "Default")
      (node (ref "J18") (pin "5") (pinfunction "INV_5") (pintype "passive"))
    )
    (net (code "75") (name "unconnected-(J18-NC-Pad8)") (class "Default")
      (node (ref "J18") (pin "8") (pinfunction "NC_8") (pintype "passive"))
    )
    (net (code "76") (name "unconnected-(J18-SLW-Pad4)") (class "Default")
      (node (ref "J18") (pin "4") (pinfunction "SLW_4") (pintype "passive"))
    )
    (net (code "77") (name "unconnected-(P0-3.0-Pad1)") (class "Default")
      (node (ref "P0") (pin "1") (pinfunction "3.0_1") (pintype "passive"))
    )
    (net (code "78") (name "unconnected-(P0-3.1-Pad2)") (class "Default")
      (node (ref "P0") (pin "2") (pinfunction "3.1_2") (pintype "passive"))
    )
    (net (code "79") (name "unconnected-(P0-3.2-Pad3)") (class "Default")
      (node (ref "P0") (pin "3") (pinfunction "3.2_3") (pintype "passive"))
    )
    (net (code "80") (name "unconnected-(P0-3.3-Pad4)") (class "Default")
      (node (ref "P0") (pin "4") (pinfunction "3.3_4") (pintype "passive"))
    )
    (net (code "81") (name "unconnected-(P0-3.5-Pad6)") (class "Default")
      (node (ref "P0") (pin "6") (pinfunction "3.5_6") (pintype "passive"))
    )
    (net (code "82") (name "unconnected-(P0-3.6-Pad7)") (class "Default")
      (node (ref "P0") (pin "7") (pinfunction "3.6_7") (pintype "passive"))
    )
    (net (code "83") (name "unconnected-(P0-3.7-Pad8)") (class "Default")
      (node (ref "P0") (pin "8") (pinfunction "3.7_8") (pintype "passive"))
    )
    (net (code "84") (name "unconnected-(P1-1.2-Pad3)") (class "Default")
      (node (ref "P1") (pin "3") (pinfunction "1.2_3") (pintype "passive"))
    )
    (net (code "85") (name "unconnected-(P1-1.4-Pad5)") (class "Default")
      (node (ref "P1") (pin "5") (pinfunction "1.4_5") (pintype "passive"))
    )
    (net (code "86") (name "unconnected-(P1-1.5-Pad6)") (class "Default")
      (node (ref "P1") (pin "6") (pinfunction "1.5_6") (pintype "passive"))
    )
    (net (code "87") (name "unconnected-(P1-1.6-Pad7)") (class "Default")
      (node (ref "P1") (pin "7") (pinfunction "1.6_7") (pintype "passive"))
    )
    (net (code "88") (name "unconnected-(P1-1.7-Pad8)") (class "Default")
      (node (ref "P1") (pin "8") (pinfunction "1.7_8") (pintype "passive"))
    )
    (net (code "89") (name "unconnected-(P2-2.0-Pad1)") (class "Default")
      (node (ref "P2") (pin "1") (pinfunction "2.0_1") (pintype "passive"))
    )
    (net (code "90") (name "unconnected-(P2-2.1-Pad2)") (class "Default")
      (node (ref "P2") (pin "2") (pinfunction "2.1_2") (pintype "passive"))
    )
    (net (code "91") (name "unconnected-(P2-2.2-Pad3)") (class "Default")
      (node (ref "P2") (pin "3") (pinfunction "2.2_3") (pintype "passive"))
    )
    (net (code "92") (name "unconnected-(P2-2.3-Pad4)") (class "Default")
      (node (ref "P2") (pin "4") (pinfunction "2.3_4") (pintype "passive"))
    )
    (net (code "93") (name "unconnected-(P2-2.4-Pad5)") (class "Default")
      (node (ref "P2") (pin "5") (pinfunction "2.4_5") (pintype "passive"))
    )
    (net (code "94") (name "unconnected-(P2-2.7-Pad8)") (class "Default")
      (node (ref "P2") (pin "8") (pinfunction "2.7_8") (pintype "passive"))
    )
    (net (code "95") (name "unconnected-(P3-3.0-Pad1)") (class "Default")
      (node (ref "P3") (pin "1") (pinfunction "3.0_1") (pintype "passive"))
    )
    (net (code "96") (name "unconnected-(P3-3.1-Pad2)") (class "Default")
      (node (ref "P3") (pin "2") (pinfunction "3.1_2") (pintype "passive"))
    )
    (net (code "97") (name "unconnected-(P3-3.3-Pad4)") (class "Default")
      (node (ref "P3") (pin "4") (pinfunction "3.3_4") (pintype "passive"))
    )
    (net (code "98") (name "unconnected-(P3-3.4-Pad5)") (class "Default")
      (node (ref "P3") (pin "5") (pinfunction "3.4_5") (pintype "passive"))
    )
    (net (code "99") (name "unconnected-(P3-3.5-Pad6)") (class "Default")
      (node (ref "P3") (pin "6") (pinfunction "3.5_6") (pintype "passive"))
    )
    (net (code "100") (name "unconnected-(P3-3.6-Pad7)") (class "Default")
      (node (ref "P3") (pin "7") (pinfunction "3.6_7") (pintype "passive"))
    )
    (net (code "101") (name "unconnected-(P12-12.0-Pad1)") (class "Default")
      (node (ref "P12") (pin "1") (pinfunction "12.0_1") (pintype "passive"))
    )
    (net (code "102") (name "unconnected-(P12-12.1-Pad2)") (class "Default")
      (node (ref "P12") (pin "2") (pinfunction "12.1_2") (pintype "passive"))
    )
    (net (code "103") (name "unconnected-(P12-12.2-Pad3)") (class "Default")
      (node (ref "P12") (pin "3") (pinfunction "12.2_3") (pintype "passive"))
    )
    (net (code "104") (name "unconnected-(P12-12.3-Pad4)") (class "Default")
      (node (ref "P12") (pin "4") (pinfunction "12.3_4") (pintype "passive"))
    )
    (net (code "105") (name "unconnected-(P12-12.4-Pad5)") (class "Default")
      (node (ref "P12") (pin "5") (pinfunction "12.4_5") (pintype "passive"))
    )
    (net (code "106") (name "unconnected-(P12-12.5-Pad6)") (class "Default")
      (node (ref "P12") (pin "6") (pinfunction "12.5_6") (pintype "passive"))
    )
    (net (code "107") (name "unconnected-(P12-12.6-Pad7)") (class "Default")
      (node (ref "P12") (pin "7") (pinfunction "12.6_7") (pintype "passive"))
    )
    (net (code "108") (name "unconnected-(P12-12.7-Pad8)") (class "Default")
      (node (ref "P12") (pin "8") (pinfunction "12.7_8") (pintype "passive"))
    )
    (net (code "109") (name "unconnected-(P15-15.1-Pad2)") (class "Default")
      (node (ref "P15") (pin "2") (pinfunction "15.1_2") (pintype "passive"))
    )
    (net (code "110") (name "unconnected-(P15-15.2-Pad3)") (class "Default")
      (node (ref "P15") (pin "3") (pinfunction "15.2_3") (pintype "passive"))
    )
    (net (code "111") (name "unconnected-(P15-ENCD-Pad7)") (class "Default")
      (node (ref "P15") (pin "7") (pinfunction "ENCD_7") (pintype "passive"))
    )
    (net (code "112") (name "unconnected-(P15-ENCD-Pad8)") (class "Default")
      (node (ref "P15") (pin "8") (pinfunction "ENCD_8") (pintype "passive"))
    )
    (net (code "113") (name "unconnected-(R2-Pad1)") (class "Default")
      (node (ref "R2") (pin "1") (pinfunction "1_1") (pintype "passive"))
    )
    (net (code "114") (name "unconnected-(R3-Pad1)") (class "Default")
      (node (ref "R3") (pin "1") (pinfunction "1_1") (pintype "passive"))
    )
    (net (code "115") (name "unconnected-(R30-Pad1)") (class "Default")
      (node (ref "R30") (pin "1") (pinfunction "1_1") (pintype "passive"))
    )
  )
)
